# PrototypeBoardV1C.net
KiCad netlist of a schematic drawn in EasyEDA Pro
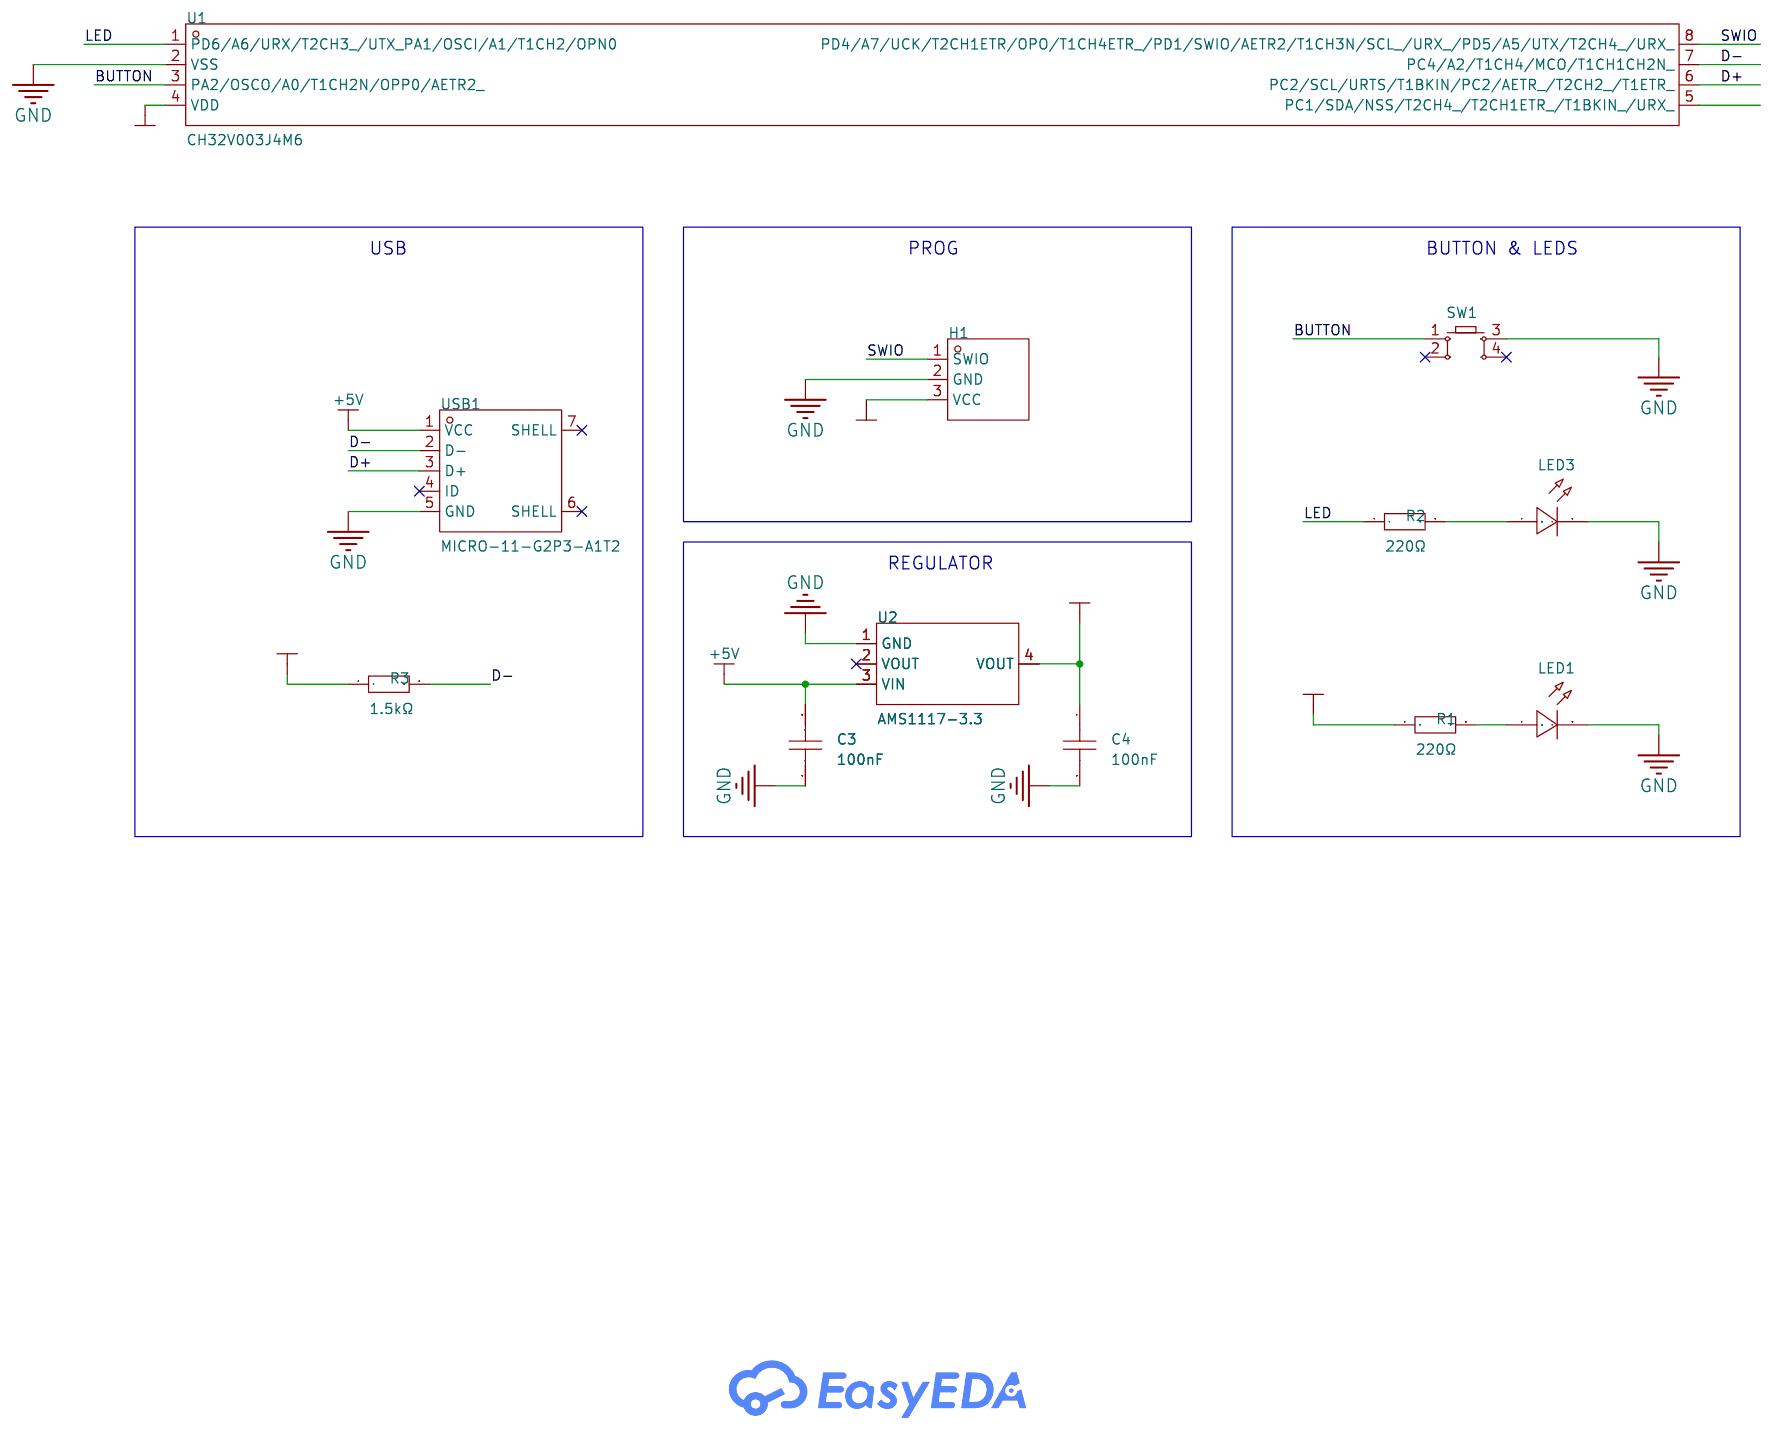
[diagram p0: schematic sheet]

(export (version "E")
  (design (tool "Eeschema 10.0.6"))
  (components
    (comp (ref "C3")
      (value "100nF")
      (footprint "easyedapro:CAP-TH_L5.8-W3.0-P4.7-D0.45")
      (fields (field (name "Manufacturer Part") "1C10Z5U104M050B") (field (name "Manufacturer") "VISHAY(威世)"))
      (libsource (lib "easyedapro") (part "1C10Z5U104M050B"))
    )
    (comp (ref "C4")
      (value "100nF")
      (footprint "easyedapro:CAP-TH_L5.8-W3.0-P4.7-D0.45")
      (fields (field (name "Manufacturer Part") "1C10Z5U104M050B") (field (name "Manufacturer") "VISHAY(威世)"))
      (libsource (lib "easyedapro") (part "1C10Z5U104M050B"))
    )
    (comp (ref "H1")
      (value "~")
      (footprint "easyedapro:HDR-TH_3P-P2.54-V-M")
      (libsource (lib "easyedapro") (part "PZ254V-11-03P_C2937625"))
    )
    (comp (ref "LED1")
      (value "~")
      (footprint "easyedapro:LED-TH_BD3.0-P2.54-FD")
      (libsource (lib "easyedapro") (part "LED_TH-R"))
    )
    (comp (ref "LED3")
      (value "~")
      (footprint "easyedapro:LED-TH_BD5.0-P2.54-L-RD_WHITE")
      (libsource (lib "easyedapro") (part "LED_TH-B"))
    )
    (comp (ref "R1")
      (value "220Ω")
      (footprint "easyedapro:RES-TH_BD1.8-L3.2-P7.20-D0.4")
      (libsource (lib "easyedapro") (part "Res"))
    )
    (comp (ref "R2")
      (value "220Ω")
      (footprint "easyedapro:RES-TH_BD1.8-L3.2-P7.20-D0.4")
      (libsource (lib "easyedapro") (part "Res"))
    )
    (comp (ref "R3")
      (value "1.5kΩ")
      (footprint "easyedapro:RES-TH_BD1.8-L3.2-P7.20-D0.4")
      (libsource (lib "easyedapro") (part "Res"))
    )
    (comp (ref "SW1")
      (value "~")
      (footprint "easyedapro:KEY-TH_4P-L6.0-W6.0-P3.90-LS6.5")
      (libsource (lib "easyedapro") (part "轻触按键"))
    )
    (comp (ref "U1")
      (value "CH32V003J4M6")
      (footprint "easyedapro:SOP-8_L4.9-W3.8-P1.27-LS6.0-BL")
      (fields (field (name "Manufacturer") "WCH(南京沁恒)"))
      (libsource (lib "easyedapro") (part "CH32V003J4M6_C5346354"))
    )
    (comp (ref "U2")
      (value "AMS1117-3.3")
      (footprint "easyedapro:SOT-223-3_L6.5-W3.4-P2.30-LS7.0-BR")
      (fields (field (name "Manufacturer") "AMS"))
      (libsource (lib "easyedapro") (part "AMS1117-3.3"))
    )
    (comp (ref "USB1")
      (value "MICRO-11-G2P3-A1T2")
      (footprint "easyedapro:MICRO-USB-SMD_MICRO-12-G2P3-A1T2")
      (fields (field (name "Manufacturer") "Yuandi(元迪)"))
      (libsource (lib "easyedapro") (part "MICRO-11-G2P3-A1T2"))
    )
  )
  (nets
    (net (code "1") (name "+3.3V") (class "Default")
      (node (ref "C4") (pin "1") (pinfunction "1_1") (pintype "unspecified"))
      (node (ref "H1") (pin "3") (pinfunction "VCC_3") (pintype "unspecified"))
      (node (ref "R1") (pin "1") (pinfunction "1_1") (pintype "input"))
      (node (ref "R3") (pin "1") (pinfunction "1_1") (pintype "input"))
      (node (ref "U1") (pin "4") (pinfunction "VDD_4") (pintype "unspecified"))
      (node (ref "U2") (pin "4") (pinfunction "VOUT_4") (pintype "unspecified"))
    )
    (net (code "2") (name "+5V") (class "Default")
      (node (ref "C3") (pin "2") (pinfunction "2_2") (pintype "unspecified"))
      (node (ref "U2") (pin "3") (pinfunction "VIN_3") (pintype "unspecified"))
      (node (ref "USB1") (pin "1") (pinfunction "VCC_1") (pintype "unspecified"))
    )
    (net (code "3") (name "/BUTTON") (class "Default")
      (node (ref "SW1") (pin "1") (pinfunction "1_1") (pintype "input"))
      (node (ref "U1") (pin "3") (pinfunction "PA2/OSCO/A0/T1CH2N/OPP0/AETR2__3") (pintype "unspecified"))
    )
    (net (code "4") (name "/D+") (class "Default")
      (node (ref "U1") (pin "6") (pinfunction "PC2/SCL/URTS/T1BKIN/PC2/AETR_/T2CH2_/T1ETR__6") (pintype "unspecified"))
      (node (ref "USB1") (pin "3") (pinfunction "D+_3") (pintype "unspecified"))
    )
    (net (code "5") (name "/D-") (class "Default")
      (node (ref "R3") (pin "2") (pinfunction "2_2") (pintype "input"))
      (node (ref "U1") (pin "7") (pinfunction "PC4/A2/T1CH4/MCO/T1CH1CH2N__7") (pintype "unspecified"))
      (node (ref "USB1") (pin "2") (pinfunction "D-_2") (pintype "unspecified"))
    )
    (net (code "6") (name "/LED") (class "Default")
      (node (ref "R2") (pin "1") (pinfunction "1_1") (pintype "input"))
      (node (ref "U1") (pin "1") (pinfunction "PD6/A6/URX/T2CH3_/UTX_PA1/OSCI/A1/T1CH2/OPN0_1") (pintype "unspecified"))
    )
    (net (code "7") (name "/SWIO") (class "Default")
      (node (ref "H1") (pin "1") (pinfunction "SWIO_1") (pintype "unspecified"))
      (node (ref "U1") (pin "8") (pinfunction "PD4/A7/UCK/T2CH1ETR/OPO/T1CH4ETR_/PD1/SWIO/AETR2/T1CH3N/SCL_/URX_/PD5/A5/UTX/T2CH4_/URX__8") (pintype "unspecified"))
    )
    (net (code "8") (name "GND") (class "Default")
      (node (ref "C3") (pin "1") (pinfunction "1_1") (pintype "unspecified"))
      (node (ref "C4") (pin "2") (pinfunction "2_2") (pintype "unspecified"))
      (node (ref "H1") (pin "2") (pinfunction "GND_2") (pintype "unspecified"))
      (node (ref "LED1") (pin "2") (pinfunction "A_2") (pintype "input"))
      (node (ref "LED3") (pin "2") (pinfunction "A_2") (pintype "input"))
      (node (ref "SW1") (pin "3") (pinfunction "3_3") (pintype "input"))
      (node (ref "U1") (pin "2") (pinfunction "VSS_2") (pintype "unspecified"))
      (node (ref "U2") (pin "1") (pinfunction "GND_1") (pintype "unspecified"))
      (node (ref "USB1") (pin "5") (pinfunction "GND_5") (pintype "unspecified"))
    )
    (net (code "9") (name "Net-(LED1-C)") (class "Default")
      (node (ref "LED1") (pin "1") (pinfunction "C_1") (pintype "input"))
      (node (ref "R1") (pin "2") (pinfunction "2_2") (pintype "input"))
    )
    (net (code "10") (name "Net-(LED3-C)") (class "Default")
      (node (ref "LED3") (pin "1") (pinfunction "C_1") (pintype "input"))
      (node (ref "R2") (pin "2") (pinfunction "2_2") (pintype "input"))
    )
    (net (code "11") (name "unconnected-(SW1-Pad2)") (class "Default")
      (node (ref "SW1") (pin "2") (pinfunction "2_2") (pintype "input+no_connect"))
    )
    (net (code "12") (name "unconnected-(SW1-Pad4)") (class "Default")
      (node (ref "SW1") (pin "4") (pinfunction "4_4") (pintype "input+no_connect"))
    )
    (net (code "13") (name "unconnected-(U1-PC1{slash}SDA{slash}NSS{slash}T2CH4_{slash}T2CH1ETR_{slash}T1BKIN_{slash}URX_-Pad5)") (class "Default")
      (node (ref "U1") (pin "5") (pinfunction "PC1/SDA/NSS/T2CH4_/T2CH1ETR_/T1BKIN_/URX__5") (pintype "unspecified"))
    )
    (net (code "14") (name "unconnected-(U2-VOUT-Pad2)") (class "Default")
      (node (ref "U2") (pin "2") (pinfunction "VOUT_2") (pintype "unspecified+no_connect"))
    )
    (net (code "15") (name "unconnected-(USB1-ID-Pad4)") (class "Default")
      (node (ref "USB1") (pin "4") (pinfunction "ID_4") (pintype "unspecified+no_connect"))
    )
    (net (code "16") (name "unconnected-(USB1-SHELL-Pad6)") (class "Default")
      (node (ref "USB1") (pin "6") (pinfunction "SHELL_6") (pintype "unspecified+no_connect"))
    )
    (net (code "17") (name "unconnected-(USB1-SHELL-Pad7)") (class "Default")
      (node (ref "USB1") (pin "7") (pinfunction "SHELL_7") (pintype "unspecified+no_connect"))
    )
  )
)
